# BMS_Interface_Board.net
KiCad netlist of a schematic drawn in Altium Designer
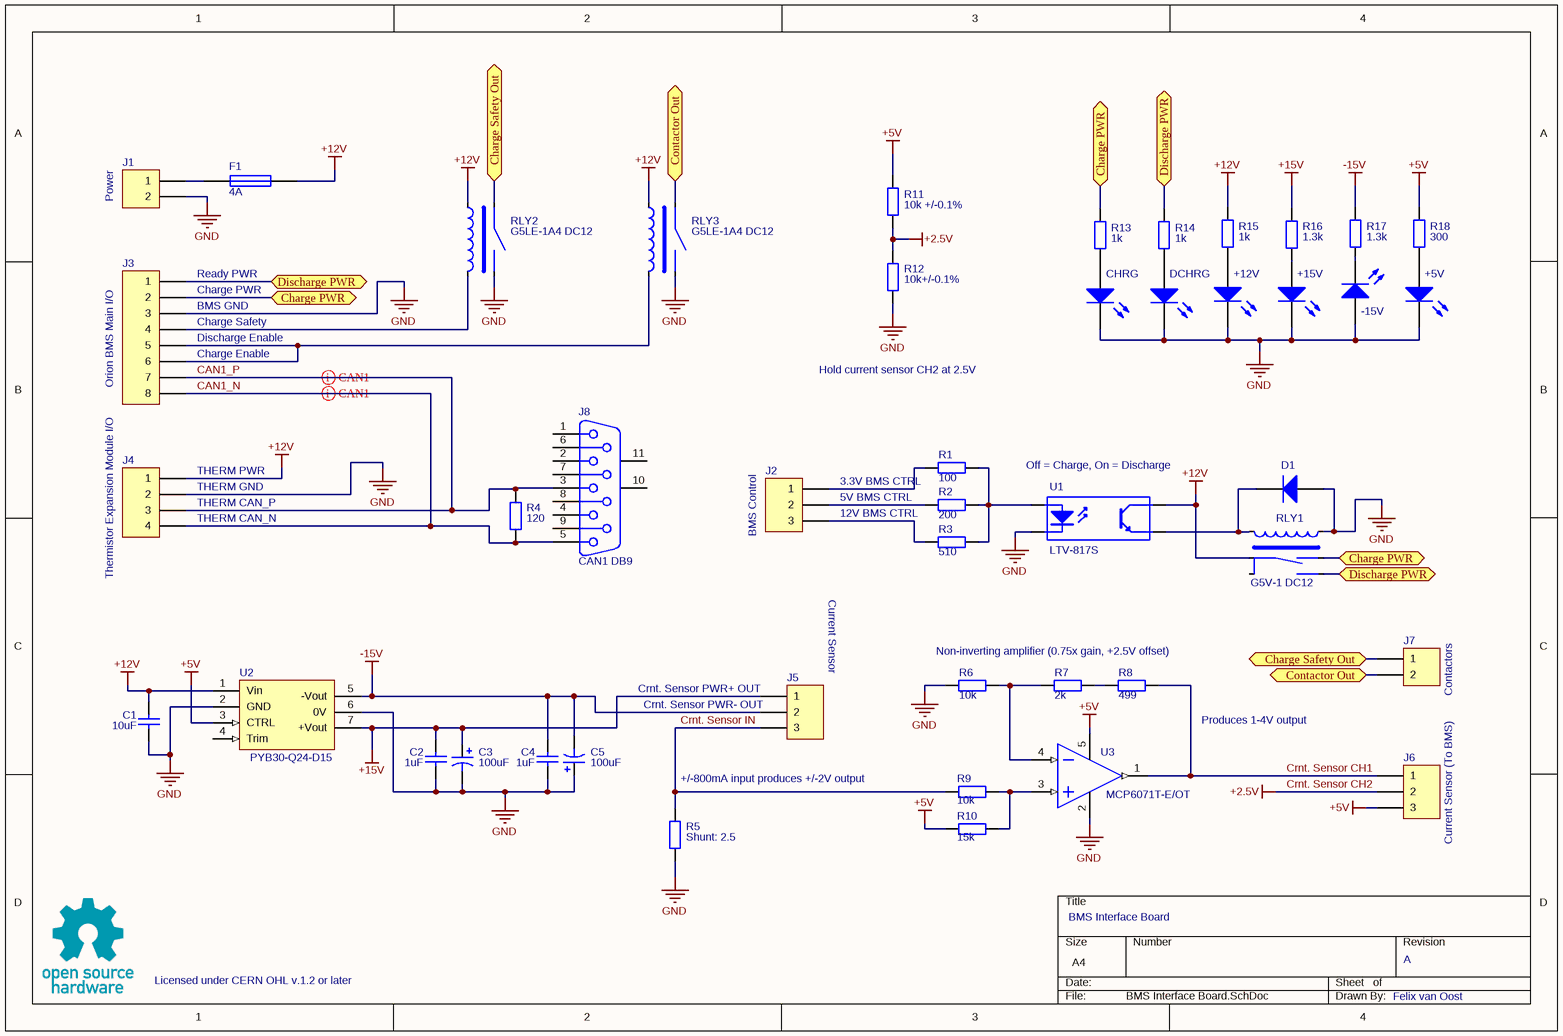
[diagram p0: BMS Interface Board.SchDoc]

(export (version "E")
  (design (tool "Eeschema 10.0.6"))
  (components
    (comp (ref "+5V")
      (value "LTST-C170GKT")
      (footprint "Lite-On LTST-C170GKT (2012)")
      (description "Typical INFRARED GaAs LED")
      (fields (field (name "PUBLISHER") "Altium Limited"))
      (libsource (lib "Miscellaneous Devices") (part "LED0"))
    )
    (comp (ref "+12V")
      (value "LTST-C170GKT")
      (footprint "Lite-On LTST-C170GKT (2012)")
      (description "Typical INFRARED GaAs LED")
      (fields (field (name "PUBLISHER") "Altium Limited"))
      (libsource (lib "Miscellaneous Devices") (part "LED0"))
    )
    (comp (ref "+15V")
      (value "LTST-C170GKT")
      (footprint "Lite-On LTST-C170GKT (2012)")
      (description "Typical INFRARED GaAs LED")
      (fields (field (name "PUBLISHER") "Altium Limited"))
      (libsource (lib "Miscellaneous Devices") (part "LED0"))
    )
    (comp (ref "-15V")
      (value "LTST-C170GKT")
      (footprint "Lite-On LTST-C170GKT (2012)")
      (description "Typical INFRARED GaAs LED")
      (fields (field (name "PUBLISHER") "Altium Limited"))
      (libsource (lib "Miscellaneous Devices") (part "LED0"))
    )
    (comp (ref "C1")
      (value "10uF")
      (footprint "Kemet Ceramic Capacitor (2012)")
      (description "Capacitor")
      (fields (field (name "Comment") "Cap") (field (name "PUBLISHER") "Altium Limited"))
      (libsource (lib "Miscellaneous Devices") (part "Cap"))
    )
    (comp (ref "C2")
      (value "1uF")
      (footprint "Kemet Ceramic Capacitor (2012)")
      (description "Capacitor")
      (fields (field (name "Comment") "Cap") (field (name "PUBLISHER") "Altium Limited"))
      (libsource (lib "Miscellaneous Devices") (part "Cap"))
    )
    (comp (ref "C3")
      (value "100uF")
      (footprint "Panasonic EEE-1EA101XAP")
      (description "Polarized Capacitor (Radial)")
      (fields (field (name "Comment") "Cap") (field (name "PUBLISHER") "Altium Limited"))
      (libsource (lib "Miscellaneous Devices") (part "Cap Pol1"))
    )
    (comp (ref "C4")
      (value "1uF")
      (footprint "Kemet Ceramic Capacitor (2012)")
      (description "Capacitor")
      (fields (field (name "Comment") "Cap") (field (name "PUBLISHER") "Altium Limited"))
      (libsource (lib "Miscellaneous Devices") (part "Cap"))
    )
    (comp (ref "C5")
      (value "100uF")
      (footprint "Panasonic EEE-1EA101XAP")
      (description "Polarized Capacitor (Radial)")
      (fields (field (name "Comment") "Cap") (field (name "PUBLISHER") "Altium Limited"))
      (libsource (lib "Miscellaneous Devices") (part "Cap Pol1"))
    )
    (comp (ref "CHRG")
      (value "LTST-C170GKT")
      (footprint "Lite-On LTST-C170GKT (2012)")
      (description "Typical INFRARED GaAs LED")
      (fields (field (name "PUBLISHER") "Altium Limited"))
      (libsource (lib "Miscellaneous Devices") (part "LED0"))
    )
    (comp (ref "D1")
      (value "S1G")
      (footprint "Fairchild S1G (DO-214AC)")
      (description "1 Amp General Purpose Rectifier")
      (fields (field (name "PUBLISHER") "Altium Limited"))
      (libsource (lib "Miscellaneous Devices") (part "Diode 1N4007"))
    )
    (comp (ref "DCHRG")
      (value "LTST-C170GKT")
      (footprint "Lite-On LTST-C170GKT (2012)")
      (description "Typical INFRARED GaAs LED")
      (fields (field (name "PUBLISHER") "Altium Limited"))
      (libsource (lib "Miscellaneous Devices") (part "LED0"))
    )
    (comp (ref "F1")
      (value "4A")
      (footprint "Littelfuse 01530007Z")
      (description "Fuse")
      (fields (field (name "PUBLISHER") "Altium Limited"))
      (libsource (lib "Miscellaneous Devices") (part "Fuse 1"))
    )
    (comp (ref "J1")
      (value "Molex Mega-Fit 172064-0002")
      (footprint "Molex Mega-Fit 172064-0002")
      (description "2-Pin Right-Angle Locking Male Header")
      (fields (field (name "DIGI-KEY PART NUMBER") "WM10391-ND"))
      (libsource (lib "BMS Interface Board") (part "Molex Mega-Fit 172064-0002"))
    )
    (comp (ref "J2")
      (value "Molex Micro-Fit 43650-0300")
      (footprint "Molex Micro-Fit 43650-0300")
      (description "3-Pin Right-Angle Locking Male Header")
      (fields (field (name "DIGI-KEY PART NUMBER") "WM1861-ND"))
      (libsource (lib "BMS Interface Board") (part "Molex Micro-Fit 43650-0300"))
    )
    (comp (ref "J3")
      (value "Molex Micro-Fit 43045-0800")
      (footprint "Molex Micro-Fit 43045-0800")
      (description "8-Pin Right-Angle Locking Male Header")
      (fields (field (name "DIGI-KEY PART NUMBER") "WM1816-ND"))
      (libsource (lib "BMS Interface Board") (part "Molex Micro-Fit 43045-0800"))
    )
    (comp (ref "J4")
      (value "Molex Micro-Fit 43045-0400")
      (footprint "Molex Micro-Fit 43045-0400")
      (description "4-Pin Right-Angle Locking Male Header")
      (fields (field (name "DIGI-KEY PART NUMBER") "WM1814-ND"))
      (libsource (lib "BMS Interface Board") (part "Molex Micro-Fit 43045-0400"))
    )
    (comp (ref "J5")
      (value "Molex Micro-Fit 43650-0300")
      (footprint "Molex Micro-Fit 43650-0300")
      (description "3-Pin Right-Angle Locking Male Header")
      (fields (field (name "DIGI-KEY PART NUMBER") "WM1861-ND"))
      (libsource (lib "") (part "Molex Micro-Fit 43650-0300_1"))
    )
    (comp (ref "J6")
      (value "Molex Micro-Fit 43650-0300")
      (footprint "Molex Micro-Fit 43650-0300")
      (description "3-Pin Right-Angle Locking Male Header")
      (fields (field (name "DIGI-KEY PART NUMBER") "WM1861-ND"))
      (libsource (lib "") (part "Molex Micro-Fit 43650-0300_1"))
    )
    (comp (ref "J7")
      (value "Molex Mega-Fit 172064-0002")
      (footprint "Molex Mega-Fit 172064-0002")
      (description "2-Pin Right-Angle Locking Male Header")
      (fields (field (name "DIGI-KEY PART NUMBER") "WM10391-ND"))
      (libsource (lib "") (part "Molex Mega-Fit 172064-0002_1"))
    )
    (comp (ref "J8")
      (value "CAN1 DB9")
      (footprint "TE Connectivity 1734354-1")
      (description "Receptacle Assembly, 9 Position, Right Angle")
      (fields (field (name "PUBLISHER") "Altium Limited"))
      (libsource (lib "Miscellaneous Connectors") (part "D Connector 9"))
    )
    (comp (ref "R1")
      (value "100")
      (footprint "Philips ERJ Series Resistor (2012)")
      (description "Resistor")
      (fields (field (name "PUBLISHER") "Altium Limited"))
      (libsource (lib "") (part "Res2_3"))
    )
    (comp (ref "R2")
      (value "200")
      (footprint "Philips ERJ Series Resistor (2012)")
      (description "Resistor")
      (fields (field (name "PUBLISHER") "Altium Limited"))
      (libsource (lib "") (part "Res2_3"))
    )
    (comp (ref "R3")
      (value "510")
      (footprint "Philips ERJ Series Resistor (2012)")
      (description "Resistor")
      (fields (field (name "PUBLISHER") "Altium Limited"))
      (libsource (lib "") (part "Res2_3"))
    )
    (comp (ref "R4")
      (value "120")
      (footprint "Philips ERJ Series Resistor (2012)")
      (description "Resistor")
      (fields (field (name "PUBLISHER") "Altium Limited"))
      (libsource (lib "Miscellaneous Devices") (part "Res2"))
    )
    (comp (ref "R5")
      (value "~")
      (footprint "Bourns PWR163S-25-2R50F (TO-252-3)")
      (description "Resistor")
      (fields (field (name "SHUNT") "2.5") (field (name "PUBLISHER") "Altium Limited"))
      (libsource (lib "Miscellaneous Devices") (part "Res2"))
    )
    (comp (ref "R6")
      (value "10k")
      (footprint "Philips ERJ Series Resistor (2012)")
      (description "Resistor")
      (fields (field (name "PUBLISHER") "Altium Limited"))
      (libsource (lib "") (part "Res2_2"))
    )
    (comp (ref "R7")
      (value "2k")
      (footprint "Philips ERJ Series Resistor (2012)")
      (description "Resistor")
      (fields (field (name "PUBLISHER") "Altium Limited"))
      (libsource (lib "") (part "Res2_2"))
    )
    (comp (ref "R8")
      (value "499")
      (footprint "Philips ERJ Series Resistor (2012)")
      (description "Resistor")
      (fields (field (name "PUBLISHER") "Altium Limited"))
      (libsource (lib "") (part "Res2_2"))
    )
    (comp (ref "R9")
      (value "10k")
      (footprint "Philips ERJ Series Resistor (2012)")
      (description "Resistor")
      (fields (field (name "PUBLISHER") "Altium Limited"))
      (libsource (lib "") (part "Res2_2"))
    )
    (comp (ref "R10")
      (value "15k")
      (footprint "Philips ERJ Series Resistor (2012)")
      (description "Resistor")
      (fields (field (name "PUBLISHER") "Altium Limited"))
      (libsource (lib "") (part "Res2_2"))
    )
    (comp (ref "R11")
      (value "10k +/-0.1%")
      (footprint "Philips ERJ Series Resistor (2012)")
      (description "Resistor")
      (fields (field (name "PUBLISHER") "Altium Limited"))
      (libsource (lib "Miscellaneous Devices") (part "Res2"))
    )
    (comp (ref "R12")
      (value "10k+/-0.1%")
      (footprint "Philips ERJ Series Resistor (2012)")
      (description "Resistor")
      (fields (field (name "PUBLISHER") "Altium Limited"))
      (libsource (lib "Miscellaneous Devices") (part "Res2"))
    )
    (comp (ref "R13")
      (value "1k")
      (footprint "Philips ERJ Series Resistor (2012)")
      (description "Resistor")
      (fields (field (name "PUBLISHER") "Altium Limited"))
      (libsource (lib "") (part "Res2_1"))
    )
    (comp (ref "R14")
      (value "1k")
      (footprint "Philips ERJ Series Resistor (2012)")
      (description "Resistor")
      (fields (field (name "PUBLISHER") "Altium Limited"))
      (libsource (lib "") (part "Res2_1"))
    )
    (comp (ref "R15")
      (value "1k")
      (footprint "Philips ERJ Series Resistor (2012)")
      (description "Resistor")
      (fields (field (name "PUBLISHER") "Altium Limited"))
      (libsource (lib "") (part "Res2_1"))
    )
    (comp (ref "R16")
      (value "1.3k")
      (footprint "Philips ERJ Series Resistor (2012)")
      (description "Resistor")
      (fields (field (name "PUBLISHER") "Altium Limited"))
      (libsource (lib "") (part "Res2_1"))
    )
    (comp (ref "R17")
      (value "1.3k")
      (footprint "Philips ERJ Series Resistor (2012)")
      (description "Resistor")
      (fields (field (name "PUBLISHER") "Altium Limited"))
      (libsource (lib "") (part "Res2_1"))
    )
    (comp (ref "R18")
      (value "300")
      (footprint "Philips ERJ Series Resistor (2012)")
      (description "Resistor")
      (fields (field (name "PUBLISHER") "Altium Limited"))
      (libsource (lib "") (part "Res2_1"))
    )
    (comp (ref "RLY1")
      (value "G5V-1 DC12")
      (footprint "Omron G5V-1 DC12")
      (description "12VDC 1A SPDT Relay")
      (fields (field (name "DIGI-KEY PART NUMBER") "Z774-ND"))
      (libsource (lib "BMS Interface Board") (part "Omron G5V-1 DC12"))
    )
    (comp (ref "RLY2")
      (value "G5LE-1A4 DC12")
      (footprint "Omron G5LE-1A4 DC12")
      (description "12VDC 10A SPST-NO Relay")
      (fields (field (name "DIGI-KEY PART NUMBER") "Z2352-ND"))
      (libsource (lib "BMS Interface Board") (part "Omron G5LE-1A4 DC12"))
    )
    (comp (ref "RLY3")
      (value "G5LE-1A4 DC12")
      (footprint "Omron G5LE-1A4 DC12")
      (description "12VDC 10A SPST-NO Relay")
      (fields (field (name "DIGI-KEY PART NUMBER") "Z2352-ND"))
      (libsource (lib "BMS Interface Board") (part "Omron G5LE-1A4 DC12"))
    )
    (comp (ref "U1")
      (value "LTV-817S")
      (footprint "Lite-On LTV-817S (4-SOP)")
      (description "4-Pin Phototransistor Optocoupler")
      (fields (field (name "PUBLISHER") "Altium Limited"))
      (libsource (lib "Miscellaneous Devices") (part "Optoisolator1"))
    )
    (comp (ref "U2")
      (value "PYB30-Q24-D15")
      (footprint "CUI PYB30-Series")
      (description "+/-15V 1A DC-DC Converter")
      (fields (field (name "DIGI-KEY PART NUMBER") "102-2941-ND"))
      (libsource (lib "BMS Interface Board") (part "CUI PYB30-Q24-D15"))
    )
    (comp (ref "U3")
      (value "MCP6071T-E/OT")
      (footprint "Microchip MCP6071T-E/OT (SOT-23-5)")
      (description "Low Offset Op-Amp")
      (fields (field (name "DIGI-KEY PART NUMBER") "MCP6071T-E/OTCT-ND"))
      (libsource (lib "BMS Interface Board") (part "Microchip MCP6071T-E/OT"))
    )
  )
  (nets
    (net (code "1") (name "+2.5V") (class "Default")
      (node (ref "J6") (pin "2") (pinfunction "2_2") (pintype "passive"))
      (node (ref "R11") (pin "1") (pinfunction "1_1") (pintype "passive"))
      (node (ref "R12") (pin "2") (pinfunction "2_2") (pintype "passive"))
    )
    (net (code "2") (name "+5V") (class "Default")
      (node (ref "J6") (pin "3") (pinfunction "3_3") (pintype "passive"))
      (node (ref "R10") (pin "2") (pinfunction "2_2") (pintype "passive"))
      (node (ref "R11") (pin "2") (pinfunction "2_2") (pintype "passive"))
      (node (ref "R18") (pin "1") (pinfunction "1_1") (pintype "passive"))
      (node (ref "U2") (pin "3") (pinfunction "CTRL_3") (pintype "input"))
      (node (ref "U3") (pin "5") (pinfunction "VDD_5") (pintype "power_in"))
    )
    (net (code "3") (name "+12V") (class "Default")
      (node (ref "C1") (pin "2") (pinfunction "2_2") (pintype "passive"))
      (node (ref "F1") (pin "1") (pinfunction "1_1") (pintype "passive"))
      (node (ref "J4") (pin "1") (pinfunction "1_1") (pintype "passive"))
      (node (ref "R15") (pin "1") (pinfunction "1_1") (pintype "passive"))
      (node (ref "RLY1") (pin "3") (pinfunction "Common_3") (pintype "passive"))
      (node (ref "RLY2") (pin "2") (pinfunction "Coil_2") (pintype "passive"))
      (node (ref "RLY3") (pin "2") (pinfunction "Coil_2") (pintype "passive"))
      (node (ref "U1") (pin "4") (pinfunction "C_4") (pintype "passive"))
      (node (ref "U2") (pin "1") (pinfunction "Vin_1") (pintype "power_in"))
    )
    (net (code "4") (name "+15V") (class "Default")
      (node (ref "C2") (pin "2") (pinfunction "2_2") (pintype "passive"))
      (node (ref "C3") (pin "1") (pinfunction "1_1") (pintype "passive"))
      (node (ref "J5") (pin "1") (pinfunction "1_1") (pintype "passive"))
      (node (ref "R16") (pin "1") (pinfunction "1_1") (pintype "passive"))
      (node (ref "U2") (pin "7") (pinfunction "+Vout_7") (pintype "power_in"))
    )
    (net (code "5") (name "-15V") (class "Default")
      (node (ref "C4") (pin "2") (pinfunction "2_2") (pintype "passive"))
      (node (ref "C5") (pin "2") (pinfunction "2_2") (pintype "passive"))
      (node (ref "J5") (pin "2") (pinfunction "2_2") (pintype "passive"))
      (node (ref "R17") (pin "1") (pinfunction "1_1") (pintype "passive"))
      (node (ref "U2") (pin "5") (pinfunction "-Vout_5") (pintype "power_in"))
    )
    (net (code "6") (name "/CAN1_N") (class "Default")
      (node (ref "J3") (pin "8") (pinfunction "8_8") (pintype "passive"))
      (node (ref "J4") (pin "4") (pinfunction "4_4") (pintype "passive"))
      (node (ref "J8") (pin "5") (pinfunction "5_5") (pintype "passive"))
      (node (ref "R4") (pin "1") (pinfunction "1_1") (pintype "passive"))
    )
    (net (code "7") (name "/CAN1_P") (class "Default")
      (node (ref "J3") (pin "7") (pinfunction "7_7") (pintype "passive"))
      (node (ref "J4") (pin "3") (pinfunction "3_3") (pintype "passive"))
      (node (ref "J8") (pin "3") (pinfunction "3_3") (pintype "passive"))
      (node (ref "R4") (pin "2") (pinfunction "2_2") (pintype "passive"))
    )
    (net (code "8") (name "/Charge PWR") (class "Default")
      (node (ref "J3") (pin "2") (pinfunction "2_2") (pintype "passive"))
      (node (ref "R13") (pin "1") (pinfunction "1_1") (pintype "passive"))
      (node (ref "RLY1") (pin "1") (pinfunction "N/C_1") (pintype "passive"))
    )
    (net (code "9") (name "/Charge Safety Out") (class "Default")
      (node (ref "J7") (pin "1") (pinfunction "1_1") (pintype "passive"))
      (node (ref "RLY2") (pin "1") (pinfunction "COM_1") (pintype "passive"))
    )
    (net (code "10") (name "/Contactor Out") (class "Default")
      (node (ref "J7") (pin "2") (pinfunction "2_2") (pintype "passive"))
      (node (ref "RLY3") (pin "1") (pinfunction "COM_1") (pintype "passive"))
    )
    (net (code "11") (name "/Crnt. Sensor CH1") (class "Default")
      (node (ref "J6") (pin "1") (pinfunction "1_1") (pintype "passive"))
      (node (ref "R8") (pin "1") (pinfunction "1_1") (pintype "passive"))
      (node (ref "U3") (pin "1") (pinfunction "Vout_1") (pintype "output"))
    )
    (net (code "12") (name "/Crnt. Sensor IN") (class "Default")
      (node (ref "J5") (pin "3") (pinfunction "3_3") (pintype "passive"))
      (node (ref "R5") (pin "2") (pinfunction "2_2") (pintype "passive"))
      (node (ref "R9") (pin "2") (pinfunction "2_2") (pintype "passive"))
    )
    (net (code "13") (name "/Discharge PWR") (class "Default")
      (node (ref "J3") (pin "1") (pinfunction "1_1") (pintype "passive"))
      (node (ref "R14") (pin "1") (pinfunction "1_1") (pintype "passive"))
      (node (ref "RLY1") (pin "6") (pinfunction "N/O_6") (pintype "passive"))
    )
    (net (code "14") (name "GND") (class "Default")
      (node (ref "+12V") (pin "2") (pinfunction "K_2") (pintype "passive"))
      (node (ref "+15V") (pin "2") (pinfunction "K_2") (pintype "passive"))
      (node (ref "+5V") (pin "2") (pinfunction "K_2") (pintype "passive"))
      (node (ref "-15V") (pin "1") (pinfunction "A_1") (pintype "passive"))
      (node (ref "C1") (pin "1") (pinfunction "1_1") (pintype "passive"))
      (node (ref "C2") (pin "1") (pinfunction "1_1") (pintype "passive"))
      (node (ref "C3") (pin "2") (pinfunction "2_2") (pintype "passive"))
      (node (ref "C4") (pin "1") (pinfunction "1_1") (pintype "passive"))
      (node (ref "C5") (pin "1") (pinfunction "1_1") (pintype "passive"))
      (node (ref "CHRG") (pin "2") (pinfunction "K_2") (pintype "passive"))
      (node (ref "D1") (pin "1") (pinfunction "A_1") (pintype "passive"))
      (node (ref "DCHRG") (pin "2") (pinfunction "K_2") (pintype "passive"))
      (node (ref "J1") (pin "2") (pinfunction "2_2") (pintype "passive"))
      (node (ref "J3") (pin "3") (pinfunction "3_3") (pintype "passive"))
      (node (ref "J4") (pin "2") (pinfunction "2_2") (pintype "passive"))
      (node (ref "R12") (pin "1") (pinfunction "1_1") (pintype "passive"))
      (node (ref "R5") (pin "1") (pinfunction "1_1") (pintype "passive"))
      (node (ref "R6") (pin "2") (pinfunction "2_2") (pintype "passive"))
      (node (ref "RLY1") (pin "5") (pinfunction "Coil_5") (pintype "passive"))
      (node (ref "RLY2") (pin "3") (pinfunction "NO_3") (pintype "passive"))
      (node (ref "RLY3") (pin "3") (pinfunction "NO_3") (pintype "passive"))
      (node (ref "U1") (pin "2") (pinfunction "K_2") (pintype "passive"))
      (node (ref "U2") (pin "2") (pinfunction "GND_2") (pintype "power_in"))
      (node (ref "U2") (pin "6") (pinfunction "0V_6") (pintype "power_in"))
      (node (ref "U3") (pin "2") (pinfunction "VSS_2") (pintype "power_in"))
    )
    (net (code "15") (name "Net-(+5V-A)") (class "Default")
      (node (ref "+5V") (pin "1") (pinfunction "A_1") (pintype "passive"))
      (node (ref "R18") (pin "2") (pinfunction "2_2") (pintype "passive"))
    )
    (net (code "16") (name "Net-(+12V-A)") (class "Default")
      (node (ref "+12V") (pin "1") (pinfunction "A_1") (pintype "passive"))
      (node (ref "R15") (pin "2") (pinfunction "2_2") (pintype "passive"))
    )
    (net (code "17") (name "Net-(+15V-A)") (class "Default")
      (node (ref "+15V") (pin "1") (pinfunction "A_1") (pintype "passive"))
      (node (ref "R16") (pin "2") (pinfunction "2_2") (pintype "passive"))
    )
    (net (code "18") (name "Net-(-15V-K)") (class "Default")
      (node (ref "-15V") (pin "2") (pinfunction "K_2") (pintype "passive"))
      (node (ref "R17") (pin "2") (pinfunction "2_2") (pintype "passive"))
    )
    (net (code "19") (name "Net-(CHRG-A)") (class "Default")
      (node (ref "CHRG") (pin "1") (pinfunction "A_1") (pintype "passive"))
      (node (ref "R13") (pin "2") (pinfunction "2_2") (pintype "passive"))
    )
    (net (code "20") (name "Net-(D1-K)") (class "Default")
      (node (ref "D1") (pin "2") (pinfunction "K_2") (pintype "passive"))
      (node (ref "RLY1") (pin "2") (pinfunction "Coil_2") (pintype "passive"))
      (node (ref "U1") (pin "3") (pinfunction "E_3") (pintype "passive"))
    )
    (net (code "21") (name "Net-(DCHRG-A)") (class "Default")
      (node (ref "DCHRG") (pin "1") (pinfunction "A_1") (pintype "passive"))
      (node (ref "R14") (pin "2") (pinfunction "2_2") (pintype "passive"))
    )
    (net (code "22") (name "Net-(F1-Pad2)") (class "Default")
      (node (ref "F1") (pin "2") (pinfunction "2_2") (pintype "passive"))
      (node (ref "J1") (pin "1") (pinfunction "1_1") (pintype "passive"))
    )
    (net (code "23") (name "Net-(J2-Pad1)") (class "Default")
      (node (ref "J2") (pin "1") (pinfunction "1_1") (pintype "passive"))
      (node (ref "R1") (pin "1") (pinfunction "1_1") (pintype "passive"))
    )
    (net (code "24") (name "Net-(J2-Pad2)") (class "Default")
      (node (ref "J2") (pin "2") (pinfunction "2_2") (pintype "passive"))
      (node (ref "R2") (pin "1") (pinfunction "1_1") (pintype "passive"))
    )
    (net (code "25") (name "Net-(J2-Pad3)") (class "Default")
      (node (ref "J2") (pin "3") (pinfunction "3_3") (pintype "passive"))
      (node (ref "R3") (pin "1") (pinfunction "1_1") (pintype "passive"))
    )
    (net (code "26") (name "Net-(J3-Pad4)") (class "Default")
      (node (ref "J3") (pin "4") (pinfunction "4_4") (pintype "passive"))
      (node (ref "RLY2") (pin "4") (pinfunction "Coil_4") (pintype "passive"))
    )
    (net (code "27") (name "Net-(J3-Pad5)") (class "Default")
      (node (ref "J3") (pin "5") (pinfunction "5_5") (pintype "passive"))
      (node (ref "J3") (pin "6") (pinfunction "6_6") (pintype "passive"))
      (node (ref "RLY3") (pin "4") (pinfunction "Coil_4") (pintype "passive"))
    )
    (net (code "28") (name "Net-(R7-Pad1)") (class "Default")
      (node (ref "R7") (pin "1") (pinfunction "1_1") (pintype "passive"))
      (node (ref "R8") (pin "2") (pinfunction "2_2") (pintype "passive"))
    )
    (net (code "29") (name "Net-(U1-A)") (class "Default")
      (node (ref "R1") (pin "2") (pinfunction "2_2") (pintype "passive"))
      (node (ref "R2") (pin "2") (pinfunction "2_2") (pintype "passive"))
      (node (ref "R3") (pin "2") (pinfunction "2_2") (pintype "passive"))
      (node (ref "U1") (pin "1") (pinfunction "A_1") (pintype "passive"))
    )
    (net (code "30") (name "Net-(U3-Vin+)") (class "Default")
      (node (ref "R6") (pin "1") (pinfunction "1_1") (pintype "passive"))
      (node (ref "R7") (pin "2") (pinfunction "2_2") (pintype "passive"))
      (node (ref "U3") (pin "4") (pinfunction "Vin+_4") (pintype "input"))
    )
    (net (code "31") (name "Net-(U3-Vin-)") (class "Default")
      (node (ref "R10") (pin "1") (pinfunction "1_1") (pintype "passive"))
      (node (ref "R9") (pin "1") (pinfunction "1_1") (pintype "passive"))
      (node (ref "U3") (pin "3") (pinfunction "Vin-_3") (pintype "input"))
    )
    (net (code "32") (name "unconnected-(J8-MH1-Pad10)") (class "Default")
      (node (ref "J8") (pin "10") (pinfunction "MH1_10") (pintype "passive"))
    )
    (net (code "33") (name "unconnected-(J8-MH2-Pad11)") (class "Default")
      (node (ref "J8") (pin "11") (pinfunction "MH2_11") (pintype "passive"))
    )
    (net (code "34") (name "unconnected-(J8-Pad1)") (class "Default")
      (node (ref "J8") (pin "1") (pinfunction "1_1") (pintype "passive"))
    )
    (net (code "35") (name "unconnected-(J8-Pad2)") (class "Default")
      (node (ref "J8") (pin "2") (pinfunction "2_2") (pintype "passive"))
    )
    (net (code "36") (name "unconnected-(J8-Pad4)") (class "Default")
      (node (ref "J8") (pin "4") (pinfunction "4_4") (pintype "passive"))
    )
    (net (code "37") (name "unconnected-(J8-Pad6)") (class "Default")
      (node (ref "J8") (pin "6") (pinfunction "6_6") (pintype "passive"))
    )
    (net (code "38") (name "unconnected-(J8-Pad7)") (class "Default")
      (node (ref "J8") (pin "7") (pinfunction "7_7") (pintype "passive"))
    )
    (net (code "39") (name "unconnected-(J8-Pad8)") (class "Default")
      (node (ref "J8") (pin "8") (pinfunction "8_8") (pintype "passive"))
    )
    (net (code "40") (name "unconnected-(J8-Pad9)") (class "Default")
      (node (ref "J8") (pin "9") (pinfunction "9_9") (pintype "passive"))
    )
    (net (code "41") (name "unconnected-(RLY1-Common-Pad4)") (class "Default")
      (node (ref "RLY1") (pin "4") (pinfunction "Common_4") (pintype "passive"))
    )
    (net (code "42") (name "unconnected-(U2-Trim-Pad4)") (class "Default")
      (node (ref "U2") (pin "4") (pinfunction "Trim_4") (pintype "input"))
    )
  )
)
